# 20_Power_Supply.net
KiCad netlist of a schematic drawn in Altium Designer
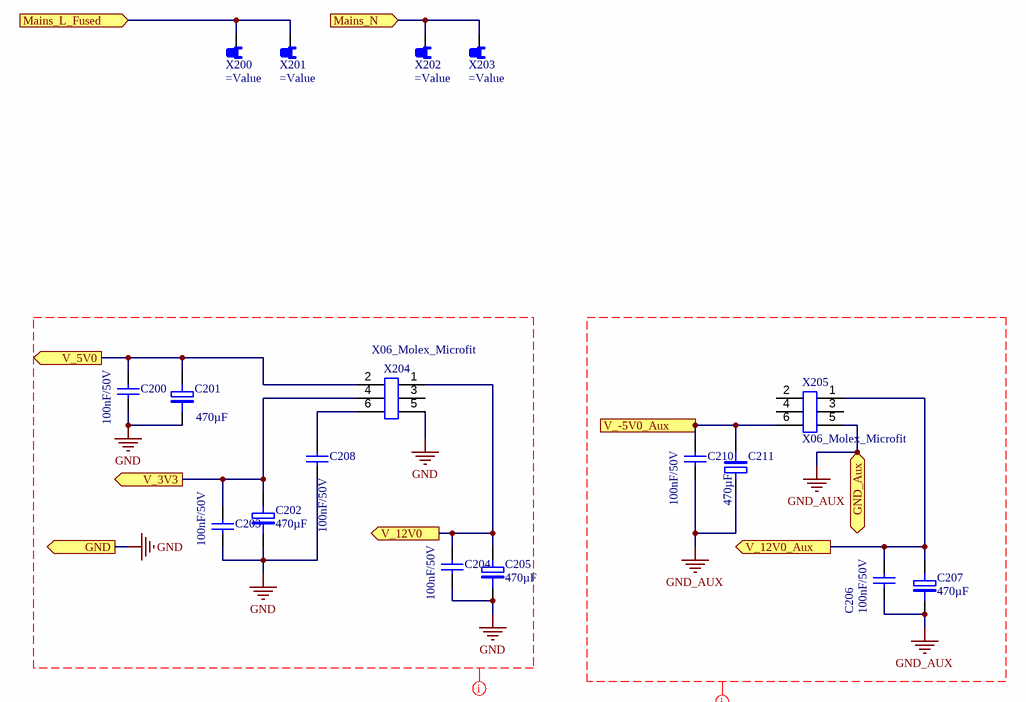
[diagram p0: 20_Power_Supply.SchDoc]

(export (version "E")
  (design (tool "Eeschema 10.0.6"))
  (components
    (comp (ref "C200")
      (value "100nF/50V")
      (footprint "EIA0603")
      (description "Generic 0603 ceramic capacitor")
      (fields (field (name "MANUFACTURER") "Open") (field (name "CREATED BY") "Hamad"))
      (libsource (lib "Amjad_Components") (part "C_Ceramic"))
    )
    (comp (ref "C201")
      (value "470µF")
      (footprint "CAPACITOR-ELKO-RM5-10x20")
      (description "470µF, 50V, Radial, 2000Hrs")
      (fields (field (name "MANUFACTURER") "Rubicon") (field (name "CREATED BY") "Hamad"))
      (libsource (lib "Amjad_Components") (part "ECAP"))
    )
    (comp (ref "C202")
      (value "470µF")
      (footprint "CAPACITOR-ELKO-RM5-10x20")
      (description "470µF, 50V, Radial, 2000Hrs")
      (fields (field (name "MANUFACTURER") "Rubicon") (field (name "CREATED BY") "Hamad"))
      (libsource (lib "Amjad_Components") (part "ECAP"))
    )
    (comp (ref "C203")
      (value "100nF/50V")
      (footprint "EIA0603")
      (description "Generic 0603 ceramic capacitor")
      (fields (field (name "MANUFACTURER") "Open") (field (name "CREATED BY") "Hamad"))
      (libsource (lib "Amjad_Components") (part "C_Ceramic"))
    )
    (comp (ref "C204")
      (value "100nF/50V")
      (footprint "EIA0603")
      (description "Generic 0603 ceramic capacitor")
      (fields (field (name "MANUFACTURER") "Open") (field (name "CREATED BY") "Hamad"))
      (libsource (lib "Amjad_Components") (part "C_Ceramic"))
    )
    (comp (ref "C205")
      (value "470µF")
      (footprint "CAPACITOR-ELKO-RM5-10x20")
      (description "470µF, 50V, Radial, 2000Hrs")
      (fields (field (name "MANUFACTURER") "Rubicon") (field (name "CREATED BY") "Hamad"))
      (libsource (lib "Amjad_Components") (part "ECAP"))
    )
    (comp (ref "C206")
      (value "100nF/50V")
      (footprint "EIA0603")
      (description "Generic 0603 ceramic capacitor")
      (fields (field (name "MANUFACTURER") "Open") (field (name "CREATED BY") "Hamad"))
      (libsource (lib "Amjad_Components") (part "C_Ceramic"))
    )
    (comp (ref "C207")
      (value "470µF")
      (footprint "CAPACITOR-ELKO-RM5-10x20")
      (description "470µF, 50V, Radial, 2000Hrs")
      (fields (field (name "MANUFACTURER") "Rubicon") (field (name "CREATED BY") "Hamad"))
      (libsource (lib "Amjad_Components") (part "ECAP"))
    )
    (comp (ref "C208")
      (value "100nF/50V")
      (footprint "EIA0603")
      (description "Generic 0603 ceramic capacitor")
      (fields (field (name "MANUFACTURER") "Open") (field (name "CREATED BY") "Hamad"))
      (libsource (lib "Amjad_Components") (part "C_Ceramic"))
    )
    (comp (ref "C210")
      (value "100nF/50V")
      (footprint "EIA0603")
      (description "Generic 0603 ceramic capacitor")
      (fields (field (name "MANUFACTURER") "Open") (field (name "CREATED BY") "Hamad"))
      (libsource (lib "Amjad_Components") (part "C_Ceramic"))
    )
    (comp (ref "C211")
      (value "470µF")
      (footprint "CAPACITOR-ELKO-RM5-10x20")
      (description "470µF, 50V, Radial, 2000Hrs")
      (fields (field (name "MANUFACTURER") "Rubicon") (field (name "CREATED BY") "Hamad"))
      (libsource (lib "Amjad_Components") (part "ECAP"))
    )
    (comp (ref "X200")
      (value "~")
      (footprint "X01_FastonPCBTab6.3mm1.8mmHole")
      (description "Faston Tab straight DIN46244T3 CuZn Sn plated, pitch 5.08mm,1.8mm locking hole")
      (fields (field (name "MANUFACTURER") "Wurth") (field (name "CREATED BY") "Hamad"))
      (libsource (lib "Amjad_Components") (part "X01_V"))
    )
    (comp (ref "X201")
      (value "~")
      (footprint "X01_FastonPCBTab6.3mm1.8mmHole")
      (description "Faston Tab straight DIN46244T3 CuZn Sn plated, pitch 5.08mm,1.8mm locking hole")
      (fields (field (name "MANUFACTURER") "Wurth") (field (name "CREATED BY") "Hamad"))
      (libsource (lib "Amjad_Components") (part "X01_V"))
    )
    (comp (ref "X202")
      (value "~")
      (footprint "X01_FastonPCBTab6.3mm1.8mmHole")
      (description "Faston Tab straight DIN46244T3 CuZn Sn plated, pitch 5.08mm,1.8mm locking hole")
      (fields (field (name "MANUFACTURER") "Wurth") (field (name "CREATED BY") "Hamad"))
      (libsource (lib "Amjad_Components") (part "X01_V"))
    )
    (comp (ref "X203")
      (value "~")
      (footprint "X01_FastonPCBTab6.3mm1.8mmHole")
      (description "Faston Tab straight DIN46244T3 CuZn Sn plated, pitch 5.08mm,1.8mm locking hole")
      (fields (field (name "MANUFACTURER") "Wurth") (field (name "CREATED BY") "Hamad"))
      (libsource (lib "Amjad_Components") (part "X01_V"))
    )
    (comp (ref "X204")
      (value "X06_Molex_Microfit")
      (footprint "X06_Molex_Microfit")
      (description "Connector Header THT 6 position 0.118\" (3.00mm) Microfit")
      (fields (field (name "MANUFACTURER") "Molex") (field (name "CREATED BY") "Hamad"))
      (libsource (lib "Amjad_Components") (part "X06_2"))
    )
    (comp (ref "X205")
      (value "X06_Molex_Microfit")
      (footprint "X06_Molex_Microfit")
      (description "Connector Header THT 6 position 0.118\" (3.00mm) Microfit")
      (fields (field (name "MANUFACTURER") "Molex") (field (name "CREATED BY") "Hamad"))
      (libsource (lib "Amjad_Components") (part "X06_2"))
    )
  )
  (nets
    (net (code "1") (name "/Mains_L_Fused") (class "Default")
      (node (ref "X200") (pin "1") (pintype "passive"))
      (node (ref "X201") (pin "1") (pintype "passive"))
    )
    (net (code "2") (name "/Mains_N") (class "Default")
      (node (ref "X202") (pin "1") (pintype "passive"))
      (node (ref "X203") (pin "1") (pintype "passive"))
    )
    (net (code "3") (name "/V_-5V0_Aux") (class "Default")
      (node (ref "C210") (pin "1") (pinfunction "1_1") (pintype "passive"))
      (node (ref "C211") (pin "2") (pintype "passive"))
      (node (ref "X205") (pin "6") (pintype "passive"))
    )
    (net (code "4") (name "/V_3V3") (class "Default")
      (node (ref "C202") (pin "1") (pintype "passive"))
      (node (ref "C203") (pin "2") (pinfunction "2_2") (pintype "passive"))
      (node (ref "X204") (pin "4") (pintype "passive"))
    )
    (net (code "5") (name "/V_5V0") (class "Default")
      (node (ref "C200") (pin "2") (pinfunction "2_2") (pintype "passive"))
      (node (ref "C201") (pin "1") (pintype "passive"))
      (node (ref "X204") (pin "2") (pintype "passive"))
    )
    (net (code "6") (name "/V_12V0") (class "Default")
      (node (ref "C204") (pin "2") (pinfunction "2_2") (pintype "passive"))
      (node (ref "C205") (pin "1") (pintype "passive"))
      (node (ref "X204") (pin "1") (pintype "passive"))
    )
    (net (code "7") (name "/V_12V0_Aux") (class "Default")
      (node (ref "C206") (pin "2") (pinfunction "2_2") (pintype "passive"))
      (node (ref "C207") (pin "1") (pintype "passive"))
      (node (ref "X205") (pin "1") (pintype "passive"))
    )
    (net (code "8") (name "GND") (class "Default")
      (node (ref "C200") (pin "1") (pinfunction "1_1") (pintype "passive"))
      (node (ref "C201") (pin "2") (pintype "passive"))
      (node (ref "C202") (pin "2") (pintype "passive"))
      (node (ref "C203") (pin "1") (pinfunction "1_1") (pintype "passive"))
      (node (ref "C204") (pin "1") (pinfunction "1_1") (pintype "passive"))
      (node (ref "C205") (pin "2") (pintype "passive"))
      (node (ref "C208") (pin "2") (pinfunction "2_2") (pintype "passive"))
      (node (ref "X204") (pin "5") (pintype "passive"))
    )
    (net (code "9") (name "GND_AUX") (class "Default")
      (node (ref "C206") (pin "1") (pinfunction "1_1") (pintype "passive"))
      (node (ref "C207") (pin "2") (pintype "passive"))
      (node (ref "C210") (pin "2") (pinfunction "2_2") (pintype "passive"))
      (node (ref "C211") (pin "1") (pintype "passive"))
      (node (ref "X205") (pin "5") (pintype "passive"))
    )
    (net (code "10") (name "Net-(C208-Pad1)") (class "Default")
      (node (ref "C208") (pin "1") (pinfunction "1_1") (pintype "passive"))
      (node (ref "X204") (pin "6") (pintype "passive"))
    )
    (net (code "11") (name "unconnected-(X204-Pad3)") (class "Default")
      (node (ref "X204") (pin "3") (pintype "passive"))
    )
    (net (code "12") (name "unconnected-(X205-Pad2)") (class "Default")
      (node (ref "X205") (pin "2") (pintype "passive"))
    )
    (net (code "13") (name "unconnected-(X205-Pad3)") (class "Default")
      (node (ref "X205") (pin "3") (pintype "passive"))
    )
    (net (code "14") (name "unconnected-(X205-Pad4)") (class "Default")
      (node (ref "X205") (pin "4") (pintype "passive"))
    )
  )
)
